# Power_Management.net
KiCad netlist of a schematic drawn in Altium Designer
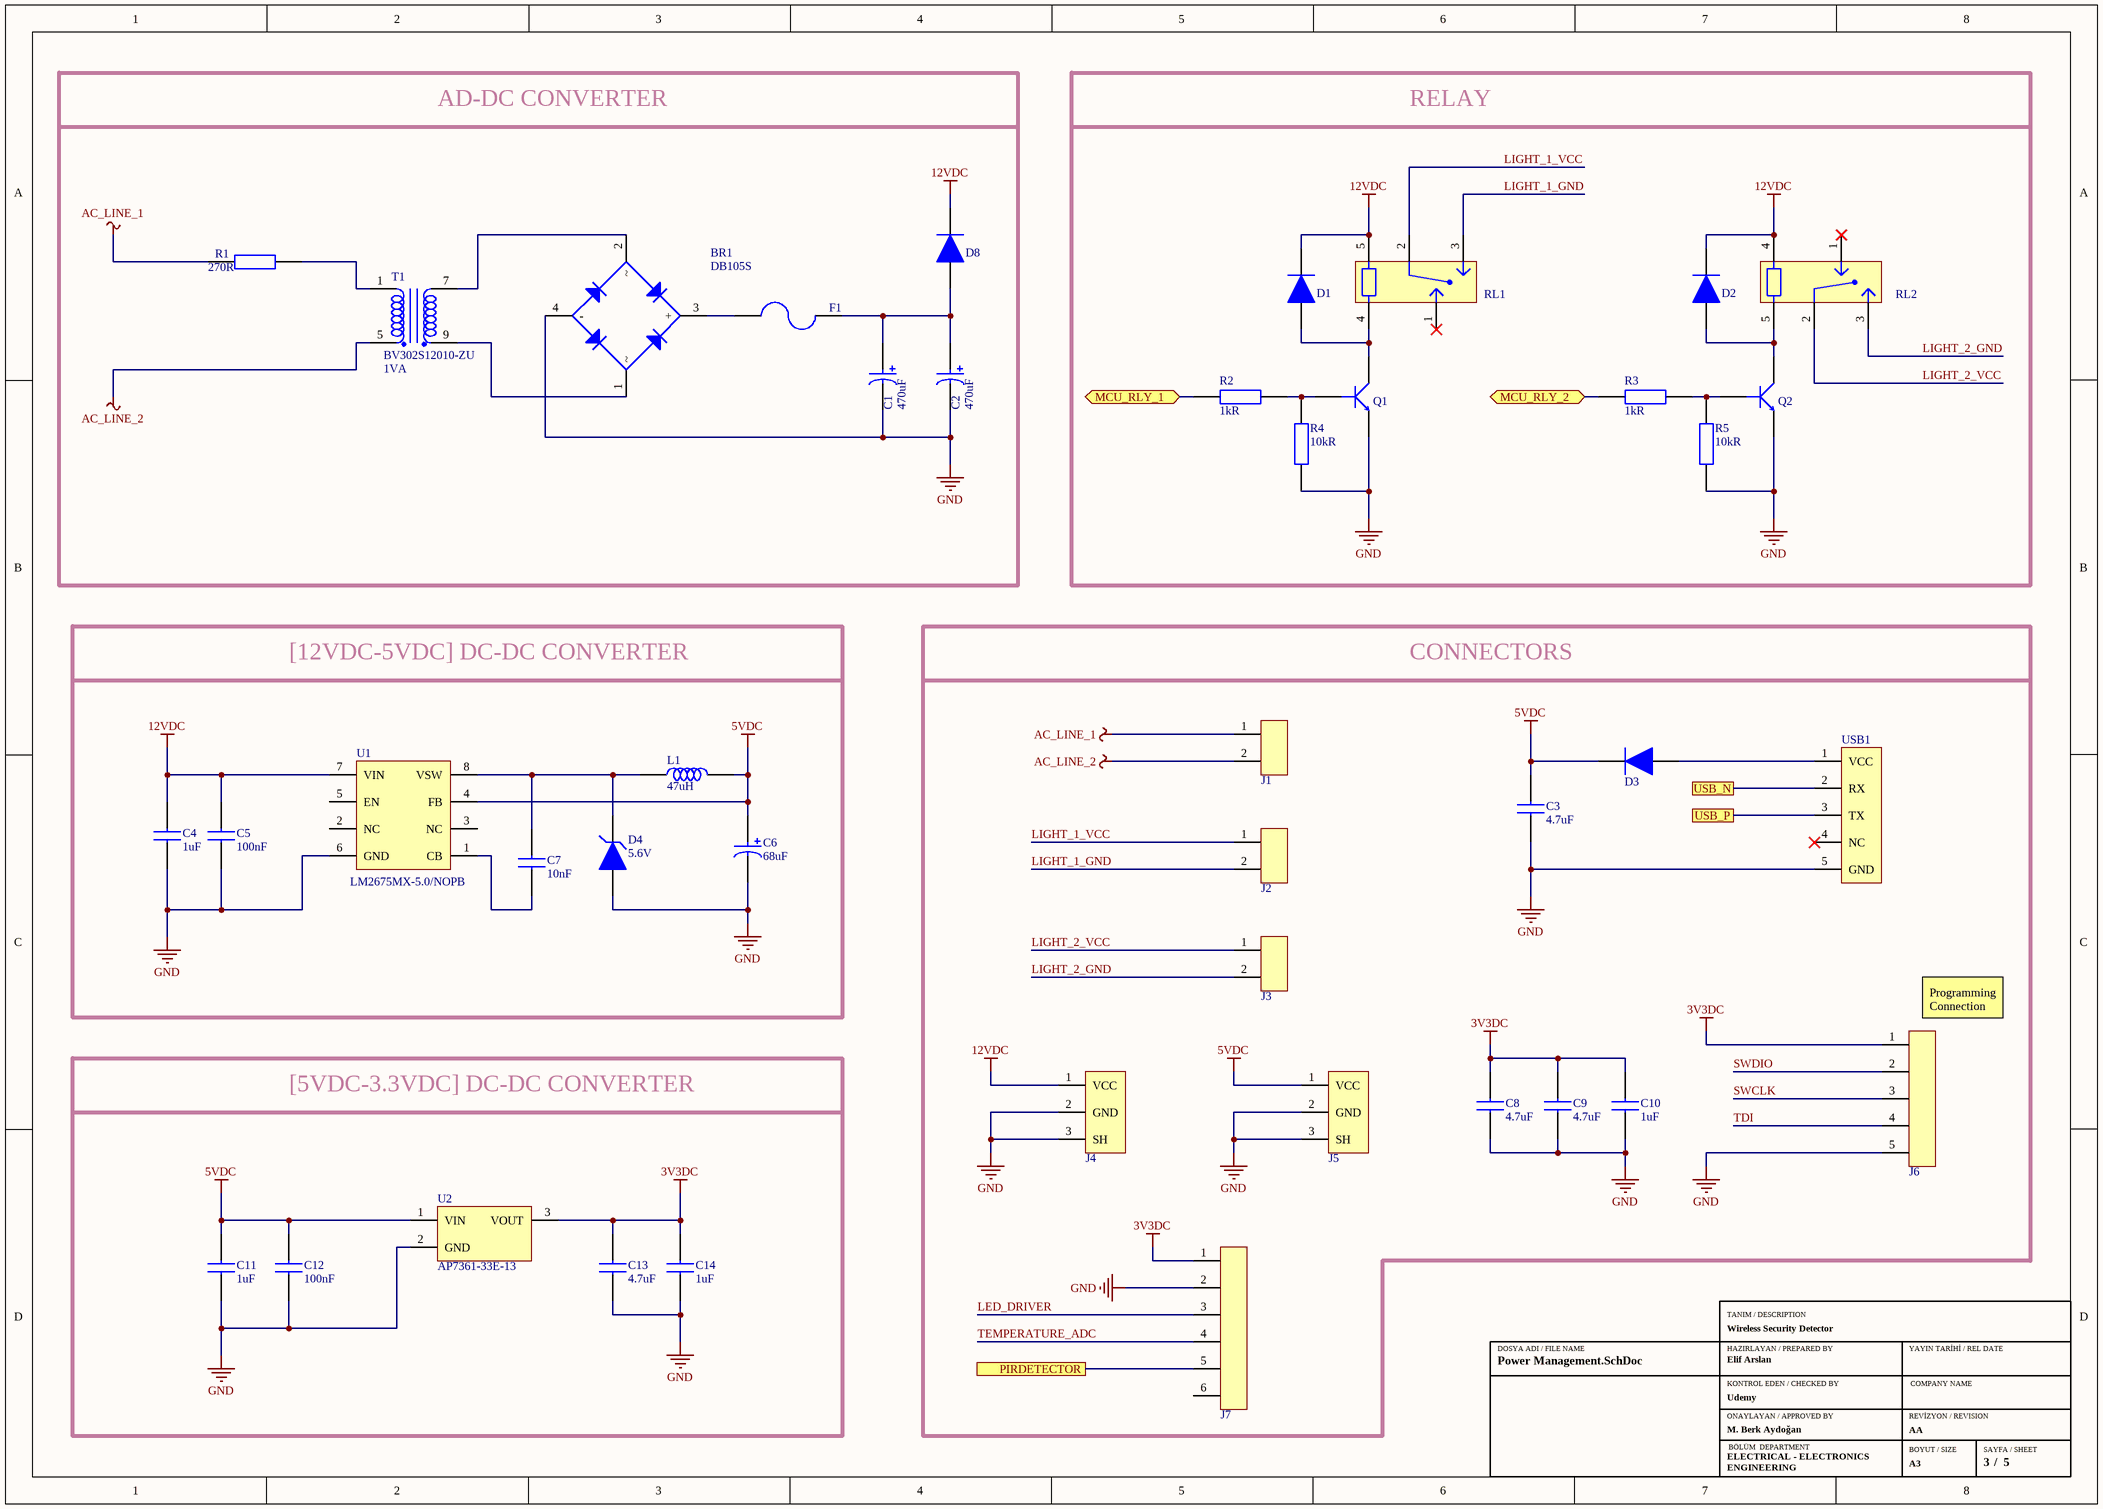
[diagram p0: Power Management.SchDoc]

(export (version "E")
  (design (tool "Eeschema 10.0.6"))
  (components
    (comp (ref "BR1")
      (value "DB105S")
      (footprint "DB105S")
      (description "Bridge Rect 1PHASE 600V 1A Db-s")
      (fields (field (name "MANUFACTURER") "Sangdest Microelectronics"))
      (libsource (lib "UDEMY_Library") (part "DB105S"))
    )
    (comp (ref "C1")
      (value "ESH477M050AL3AA")
      (footprint "CAP_RADIAL_D10_P5")
      (description "CAP ALUM 470UF 20% 50V RADIAL")
      (fields
        (field (name "MANUFACTURER") "KEMET")
        (field (name "TOLERANCE") "20%")
        (field (name "CAPACITANCE") "470uF")
      )
      (libsource (lib "UDEMY_Library") (part "CAP ALU ELEC 470uF 50V"))
    )
    (comp (ref "C2")
      (value "ESH477M050AL3AA")
      (footprint "CAP_RADIAL_D10_P5")
      (description "CAP ALUM 470UF 20% 50V RADIAL")
      (fields
        (field (name "MANUFACTURER") "KEMET")
        (field (name "TOLERANCE") "20%")
        (field (name "CAPACITANCE") "470uF")
      )
      (libsource (lib "UDEMY_Library") (part "CAP ALU ELEC 470uF 50V"))
    )
    (comp (ref "C3")
      (value "CL21A475KAQNNNE")
      (footprint "CAP_0805")
      (description "CAP CER 4.7UF 25V X5R %10 0805")
      (fields
        (field (name "MANUFACTURER") "Samsung")
        (field (name "TOLERANCE") "10%")
        (field (name "CAPACITANCE") "4.7uF")
      )
      (libsource (lib "UDEMY_Library") (part "CAP CER  4.7uF 0805"))
    )
    (comp (ref "C4")
      (value "CL21B105KBFNNNE")
      (footprint "CAP_0805")
      (description "CAP CER 1UF %10 50V 0805")
      (fields
        (field (name "MANUFACTURER") "Samsung")
        (field (name "TOLERANCE") "10%")
        (field (name "CAPACITANCE") "1uF")
      )
      (libsource (lib "UDEMY_Library") (part "CAP CER 1uF 0805"))
    )
    (comp (ref "C5")
      (value "CL21B104KBCNNNC")
      (footprint "CAP_0805")
      (description "CAP CER 0.1UF  %10 50V X7R  0805")
      (fields
        (field (name "MANUFACTURER") "Samsung")
        (field (name "TOLERANCE") "10%")
        (field (name "CAPACITANCE") "100nF")
      )
      (libsource (lib "UDEMY_Library") (part "CAP CER 100nF 0805"))
    )
    (comp (ref "C6")
      (value "EEV686M035A9HAA")
      (footprint "CAP_EEVseries")
      (description "CAP ALUM 68UF 20% 35V SMD")
      (fields
        (field (name "MANUFACTURER") "KEMET")
        (field (name "TOLERANCE") "20%")
        (field (name "CAPACITANCE") "68uF")
      )
      (libsource (lib "UDEMY_Library") (part "CAP ALU 68uF"))
    )
    (comp (ref "C7")
      (value "0603B103K160CT")
      (footprint "CAP_0603")
      (description "CAP CER 10nF %10 0603")
      (fields
        (field (name "MANUFACTURER") "Walsin Technologies")
        (field (name "TOLERANCE") "10%")
        (field (name "CAPACITANCE") "10nF")
      )
      (libsource (lib "UDEMY_Library") (part "CAP CER 10nF 0603"))
    )
    (comp (ref "C8")
      (value "CL21A475KAQNNNE")
      (footprint "CAP_0805")
      (description "CAP CER 4.7UF 25V X5R %10 0805")
      (fields
        (field (name "MANUFACTURER") "Samsung")
        (field (name "TOLERANCE") "10%")
        (field (name "CAPACITANCE") "4.7uF")
      )
      (libsource (lib "UDEMY_Library") (part "CAP CER  4.7uF 0805"))
    )
    (comp (ref "C9")
      (value "CL21A475KAQNNNE")
      (footprint "CAP_0805")
      (description "CAP CER 4.7UF 25V X5R %10 0805")
      (fields
        (field (name "MANUFACTURER") "Samsung")
        (field (name "TOLERANCE") "10%")
        (field (name "CAPACITANCE") "4.7uF")
      )
      (libsource (lib "UDEMY_Library") (part "CAP CER  4.7uF 0805"))
    )
    (comp (ref "C10")
      (value "CL21B105KBFNNNE")
      (footprint "CAP_0805")
      (description "CAP CER 1UF %10 50V 0805")
      (fields
        (field (name "MANUFACTURER") "Samsung")
        (field (name "TOLERANCE") "10%")
        (field (name "CAPACITANCE") "1uF")
      )
      (libsource (lib "UDEMY_Library") (part "CAP CER 1uF 0805"))
    )
    (comp (ref "C11")
      (value "CL21B105KBFNNNE")
      (footprint "CAP_0805")
      (description "CAP CER 1UF %10 50V 0805")
      (fields
        (field (name "MANUFACTURER") "Samsung")
        (field (name "TOLERANCE") "10%")
        (field (name "CAPACITANCE") "1uF")
      )
      (libsource (lib "UDEMY_Library") (part "CAP CER 1uF 0805"))
    )
    (comp (ref "C12")
      (value "C0603C104K4RACTU")
      (footprint "CAP_0603")
      (description "CAP CER 100nF %10 0603 SMD")
      (fields
        (field (name "MANUFACTURER") "KEMET")
        (field (name "TOLERANCE") "10%")
        (field (name "CAPACITANCE") "100nF")
      )
      (libsource (lib "UDEMY_Library") (part "CAP CER 100nF 0603"))
    )
    (comp (ref "C13")
      (value "CL21A475KAQNNNE")
      (footprint "CAP_0805")
      (description "CAP CER 4.7UF 25V X5R %10 0805")
      (fields
        (field (name "MANUFACTURER") "Samsung")
        (field (name "TOLERANCE") "10%")
        (field (name "CAPACITANCE") "4.7uF")
      )
      (libsource (lib "UDEMY_Library") (part "CAP CER  4.7uF 0805"))
    )
    (comp (ref "C14")
      (value "CL21B105KBFNNNE")
      (footprint "CAP_0805")
      (description "CAP CER 1UF %10 50V 0805")
      (fields
        (field (name "MANUFACTURER") "Samsung")
        (field (name "TOLERANCE") "10%")
        (field (name "CAPACITANCE") "1uF")
      )
      (libsource (lib "UDEMY_Library") (part "CAP CER 1uF 0805"))
    )
    (comp (ref "D1")
      (value "1N4148WS")
      (footprint "SOD323F")
      (description "VR=75V IF=150mA Trr=4ns P=200mW")
      (fields (field (name "MANUFACTURER") "ON Semiconductor / Fairchild"))
      (libsource (lib "UDEMY_Library") (part "1N4148WS"))
    )
    (comp (ref "D2")
      (value "1N4148WS")
      (footprint "SOD323F")
      (description "VR=75V IF=150mA Trr=4ns P=200mW")
      (fields (field (name "MANUFACTURER") "ON Semiconductor / Fairchild"))
      (libsource (lib "UDEMY_Library") (part "1N4148WS"))
    )
    (comp (ref "D3")
      (value "1N4148WS")
      (footprint "SOD323F")
      (description "VR=75V IF=150mA Trr=4ns P=200mW")
      (fields (field (name "MANUFACTURER") "ON Semiconductor / Fairchild"))
      (libsource (lib "UDEMY_Library") (part "1N4148WS"))
    )
    (comp (ref "D4")
      (value "1SMB5919BT3G")
      (footprint "SMB")
      (description "Zener Diode 5.6 V 3 W ±5% Surface Mount SMB")
      (fields
        (field (name "MANUFACTURER") "ON Semiconductor")
        (field (name "TOLERANCE") "5%")
        (field (name "VOLTAGE RATING (DC)") "5.6V")
      )
      (libsource (lib "UDEMY_Library") (part "1SMB5919BT3G"))
    )
    (comp (ref "D8")
      (value "1N4148WS")
      (footprint "SOD323F")
      (description "VR=75V IF=150mA Trr=4ns P=200mW")
      (fields (field (name "MANUFACTURER") "ON Semiconductor / Fairchild"))
      (libsource (lib "UDEMY_Library") (part "1N4148WS"))
    )
    (comp (ref "F1")
      (value "FUSE 3413.0216.22")
      (footprint "3413.0216.22")
      (description "1 A 32 V AC 63 V DC Fuse Board Mount (Cartridge Style Excluded) Surface Mount 1206 (3216 Metric)")
      (fields
        (field (name "MANUFACTURER") "Schurter")
        (field (name "MANUFACTURER PART NUMBER") "3413.0216.22")
      )
      (libsource (lib "UDEMY_Library") (part "FUSE 3413.0216.22"))
    )
    (comp (ref "J1")
      (value "TBP01R1-508-02BE")
      (footprint "TBP01R1-508")
      (description "2~24 Poles, Pluggable, Receptacle, Horizontal, 5.08 Pitch, Terminal Block Connector")
      (fields (field (name "MANUFACTURER") "CUI Devices"))
      (libsource (lib "UDEMY_Library") (part "TBP01R1-508-02BE"))
    )
    (comp (ref "J2")
      (value "TBP01R1-508-02BE")
      (footprint "TBP01R1-508")
      (description "2~24 Poles, Pluggable, Receptacle, Horizontal, 5.08 Pitch, Terminal Block Connector")
      (fields (field (name "MANUFACTURER") "CUI Devices"))
      (libsource (lib "UDEMY_Library") (part "TBP01R1-508-02BE"))
    )
    (comp (ref "J3")
      (value "TBP01R1-508-02BE")
      (footprint "TBP01R1-508")
      (description "2~24 Poles, Pluggable, Receptacle, Horizontal, 5.08 Pitch, Terminal Block Connector")
      (fields (field (name "MANUFACTURER") "CUI Devices"))
      (libsource (lib "UDEMY_Library") (part "TBP01R1-508-02BE"))
    )
    (comp (ref "J4")
      (value "PJ-037AH-SMT-TR")
      (footprint "JACK")
      (description "2.0 x 6.3 mm, 5.0 A, Horizontal, Surface Mount (SMT), Dc Power Jack Connector")
      (fields (field (name "MANUFACTURER") "CUI Devices"))
      (libsource (lib "UDEMY_Library") (part "PJ-037AH-SMT-TR"))
    )
    (comp (ref "J5")
      (value "PJ-037AH-SMT-TR")
      (footprint "JACK")
      (description "2.0 x 6.3 mm, 5.0 A, Horizontal, Surface Mount (SMT), Dc Power Jack Connector")
      (fields (field (name "MANUFACTURER") "CUI Devices"))
      (libsource (lib "UDEMY_Library") (part "PJ-037AH-SMT-TR"))
    )
    (comp (ref "J6")
      (value "SMH-105-02-L-S")
      (footprint "PINHEADER_1x5_RA")
      (description "5 Position Receptacle Connector 0.100\" (2.54mm) Surface Mount, Right Angle Gold")
      (fields (field (name "MANUFACTURER") "Samtec"))
      (libsource (lib "UDEMY_Library") (part "SMH-105-02-L-S"))
    )
    (comp (ref "J7")
      (value "64800611622")
      (footprint "64800611622")
      (description "1.5mm 6PIN Connector")
      (fields (field (name "MANUFACTURER") "Wurth Electronics"))
      (libsource (lib "UDEMY_Library") (part "64800611622_conn_6pin"))
    )
    (comp (ref "L1")
      (value "78438335470")
      (footprint "IND_1212")
      (description "47 µH Shielded Molded Inductor 390 mA 2.3Ohm Max 1212 (3030 Metric)")
      (fields
        (field (name "MANUFACTURER") "Wurth Electronics")
        (field (name "TOLERANCE") "30%")
        (field (name "INDUCTANCE") "47uH")
      )
      (libsource (lib "UDEMY_Library") (part "IND 47uH"))
    )
    (comp (ref "Q1")
      (value "MMBT3904-7-F")
      (footprint "SOT-23F")
      (description "Bipolar (BJT) Transistor NPN 40 V 200 mA 300MHz 300 mW Surface Mount SOT-23-3")
      (fields (field (name "MANUFACTURER") "Diodes Zetex"))
      (libsource (lib "UDEMY_Library") (part "MMBT3904-7-F"))
    )
    (comp (ref "Q2")
      (value "MMBT3904-7-F")
      (footprint "SOT-23F")
      (description "Bipolar (BJT) Transistor NPN 40 V 200 mA 300MHz 300 mW Surface Mount SOT-23-3")
      (fields (field (name "MANUFACTURER") "Diodes Zetex"))
      (libsource (lib "UDEMY_Library") (part "MMBT3904-7-F"))
    )
    (comp (ref "R1")
      (value "5WD27")
      (footprint "RES_AXIAL_W")
      (description "270 mOhms ±5% 5W Through Hole Resistor Axial - Wirewound")
      (fields
        (field (name "MANUFACTURER") "NTE Electronics")
        (field (name "TOLERANCE") "5%")
        (field (name "RESISTANCE") "270R")
      )
      (libsource (lib "UDEMY_Library") (part "5WD27"))
    )
    (comp (ref "R2")
      (value "RC0603FR-071KL")
      (footprint "RES_0603")
      (description "RES SMD 1K OHM %1 0603")
      (fields
        (field (name "MANUFACTURER") "Yageo")
        (field (name "TOLERANCE") "1%")
        (field (name "RESISTANCE") "1kR")
      )
      (libsource (lib "UDEMY_Library") (part "RES 1K OHM 0603"))
    )
    (comp (ref "R3")
      (value "RC0603FR-071KL")
      (footprint "RES_0603")
      (description "RES SMD 1K OHM %1 0603")
      (fields
        (field (name "MANUFACTURER") "Yageo")
        (field (name "TOLERANCE") "1%")
        (field (name "RESISTANCE") "1kR")
      )
      (libsource (lib "UDEMY_Library") (part "RES 1K OHM 0603"))
    )
    (comp (ref "R4")
      (value "RC0603FR-0710KL")
      (footprint "RES_0603")
      (description "RES 10K %1 OHM 0603 SMD")
      (fields
        (field (name "MANUFACTURER") "Yageo")
        (field (name "TOLERANCE") "1%")
        (field (name "RESISTANCE") "10kR")
      )
      (libsource (lib "UDEMY_Library") (part "RES 10K OHM 0603"))
    )
    (comp (ref "R5")
      (value "RC0603FR-0710KL")
      (footprint "RES_0603")
      (description "RES 10K %1 OHM 0603 SMD")
      (fields
        (field (name "MANUFACTURER") "Yageo")
        (field (name "TOLERANCE") "1%")
        (field (name "RESISTANCE") "10kR")
      )
      (libsource (lib "UDEMY_Library") (part "RES 10K OHM 0603"))
    )
    (comp (ref "RL1")
      (value "ALQ112")
      (footprint "ALQ112")
      (description "RELAY GEN PURPOSE SPDT 10A 12V")
      (fields (field (name "MANUFACTURER") "Panasonic"))
      (libsource (lib "") (part "ALQ112_1"))
    )
    (comp (ref "RL2")
      (value "ALQ112")
      (footprint "ALQ112")
      (description "RELAY GEN PURPOSE SPDT 10A 12V")
      (fields (field (name "MANUFACTURER") "Panasonic"))
      (libsource (lib "UDEMY_Library") (part "ALQ112"))
    )
    (comp (ref "T1")
      (value "BV302S12010-ZU")
      (footprint "BV302S")
      (description "230-12 Transformer 1VA")
      (fields (field (name "MANUFACTURER") "Zettler Magnetics") (field (name "RATED POWER") "1VA"))
      (libsource (lib "UDEMY_Library") (part "BV302S12010-ZU"))
    )
    (comp (ref "U1")
      (value "LM2675MX-5.0/NOPB")
      (footprint "SOIC8")
      (description "IC REG BUCK 5V 1A 8SOIC")
      (fields (field (name "MANUFACTURER") "TI National Semiconductor"))
      (libsource (lib "UDEMY_Library") (part "LM2675MX-5.0/NOPB"))
    )
    (comp (ref "U2")
      (value "AP7361-33E-13")
      (footprint "SOT-223")
      (description "AP7361 Series 3.3 V 1 A Low SMT Dropout Fixed-Mode Regulator - SOT-223")
      (fields (field (name "MANUFACTURER") "Diodes"))
      (libsource (lib "UDEMY_Library") (part "AP7361-33E-13"))
    )
    (comp (ref "USB1")
      (value "10118192-0001LF")
      (footprint "MICRO_B_USB")
      (description "CONN RCPT USB2.0 MICRO B SMD R/A")
      (fields (field (name "MANUFACTURER") "AMPHENOL ICC (FCI)"))
      (libsource (lib "UDEMY_Library") (part "Micro B USB Connector"))
    )
  )
  (nets
    (net (code "1") (name "/LED_DRIVER") (class "Default")
      (node (ref "J7") (pin "3") (pinfunction "3_3") (pintype "passive"))
    )
    (net (code "2") (name "/LIGHT_1_GND") (class "Default")
      (node (ref "J2") (pin "2") (pinfunction "2_2") (pintype "power_in"))
      (node (ref "RL1") (pin "3") (pinfunction "3_3") (pintype "passive"))
    )
    (net (code "3") (name "/LIGHT_1_VCC") (class "Default")
      (node (ref "J2") (pin "1") (pinfunction "1_1") (pintype "power_in"))
      (node (ref "RL1") (pin "2") (pinfunction "2_2") (pintype "passive"))
    )
    (net (code "4") (name "/LIGHT_2_GND") (class "Default")
      (node (ref "J3") (pin "2") (pinfunction "2_2") (pintype "power_in"))
      (node (ref "RL2") (pin "3") (pinfunction "3_3") (pintype "passive"))
    )
    (net (code "5") (name "/LIGHT_2_VCC") (class "Default")
      (node (ref "J3") (pin "1") (pinfunction "1_1") (pintype "power_in"))
      (node (ref "RL2") (pin "2") (pinfunction "2_2") (pintype "passive"))
    )
    (net (code "6") (name "/MCU_RLY_1") (class "Default")
      (node (ref "R2") (pin "1") (pinfunction "1_1") (pintype "passive"))
    )
    (net (code "7") (name "/MCU_RLY_2") (class "Default")
      (node (ref "R3") (pin "1") (pinfunction "1_1") (pintype "passive"))
    )
    (net (code "8") (name "/PIRDETECTOR") (class "Default")
      (node (ref "J7") (pin "5") (pinfunction "5_5") (pintype "passive"))
    )
    (net (code "9") (name "/SWCLK") (class "Default")
      (node (ref "J6") (pin "3") (pinfunction "3_3") (pintype "passive"))
    )
    (net (code "10") (name "/SWDIO") (class "Default")
      (node (ref "J6") (pin "2") (pinfunction "2_2") (pintype "passive"))
    )
    (net (code "11") (name "/TDI") (class "Default")
      (node (ref "J6") (pin "4") (pinfunction "4_4") (pintype "passive"))
    )
    (net (code "12") (name "/TEMPERATURE_ADC") (class "Default")
      (node (ref "J7") (pin "4") (pinfunction "4_4") (pintype "passive"))
    )
    (net (code "13") (name "/USB_N") (class "Default")
      (node (ref "USB1") (pin "2") (pinfunction "RX_2") (pintype "passive"))
    )
    (net (code "14") (name "/USB_P") (class "Default")
      (node (ref "USB1") (pin "3") (pinfunction "TX_3") (pintype "passive"))
    )
    (net (code "15") (name "3V3DC") (class "Default")
      (node (ref "C10") (pin "2") (pinfunction "2_2") (pintype "passive"))
      (node (ref "C13") (pin "2") (pinfunction "2_2") (pintype "passive"))
      (node (ref "C14") (pin "2") (pinfunction "2_2") (pintype "passive"))
      (node (ref "C8") (pin "2") (pinfunction "2_2") (pintype "passive"))
      (node (ref "C9") (pin "2") (pinfunction "2_2") (pintype "passive"))
      (node (ref "J6") (pin "1") (pinfunction "1_1") (pintype "passive"))
      (node (ref "J7") (pin "1") (pinfunction "1_1") (pintype "passive"))
      (node (ref "U2") (pin "3") (pinfunction "VOUT_3") (pintype "passive"))
    )
    (net (code "16") (name "5VDC") (class "Default")
      (node (ref "C11") (pin "2") (pinfunction "2_2") (pintype "passive"))
      (node (ref "C12") (pin "2") (pinfunction "2_2") (pintype "passive"))
      (node (ref "C3") (pin "2") (pinfunction "2_2") (pintype "passive"))
      (node (ref "C6") (pin "1") (pinfunction "1_1") (pintype "passive"))
      (node (ref "D3") (pin "1") (pinfunction "1_1") (pintype "passive"))
      (node (ref "J5") (pin "1") (pinfunction "VCC_1") (pintype "power_in"))
      (node (ref "L1") (pin "2") (pinfunction "2_2") (pintype "passive"))
      (node (ref "U1") (pin "4") (pinfunction "FB_4") (pintype "passive"))
      (node (ref "U2") (pin "1") (pinfunction "VIN_1") (pintype "passive"))
    )
    (net (code "17") (name "12VDC") (class "Default")
      (node (ref "C4") (pin "2") (pinfunction "2_2") (pintype "passive"))
      (node (ref "C5") (pin "2") (pinfunction "2_2") (pintype "passive"))
      (node (ref "D1") (pin "1") (pinfunction "1_1") (pintype "passive"))
      (node (ref "D2") (pin "1") (pinfunction "1_1") (pintype "passive"))
      (node (ref "D8") (pin "1") (pinfunction "1_1") (pintype "passive"))
      (node (ref "J4") (pin "1") (pinfunction "VCC_1") (pintype "power_in"))
      (node (ref "RL1") (pin "5") (pinfunction "5_5") (pintype "passive"))
      (node (ref "RL2") (pin "4") (pinfunction "4_4") (pintype "passive"))
      (node (ref "U1") (pin "7") (pinfunction "VIN_7") (pintype "passive"))
    )
    (net (code "18") (name "AC_LINE_1") (class "Default")
      (node (ref "J1") (pin "1") (pinfunction "1_1") (pintype "power_in"))
      (node (ref "R1") (pin "1") (pinfunction "1_1") (pintype "passive"))
    )
    (net (code "19") (name "AC_LINE_2") (class "Default")
      (node (ref "J1") (pin "2") (pinfunction "2_2") (pintype "power_in"))
      (node (ref "T1") (pin "5") (pinfunction "5_5") (pintype "passive"))
    )
    (net (code "20") (name "GND") (class "Default")
      (node (ref "BR1") (pin "4") (pinfunction "-_4") (pintype "passive"))
      (node (ref "C1") (pin "2") (pinfunction "2_2") (pintype "passive"))
      (node (ref "C10") (pin "1") (pinfunction "1_1") (pintype "passive"))
      (node (ref "C11") (pin "1") (pinfunction "1_1") (pintype "passive"))
      (node (ref "C12") (pin "1") (pinfunction "1_1") (pintype "passive"))
      (node (ref "C13") (pin "1") (pinfunction "1_1") (pintype "passive"))
      (node (ref "C14") (pin "1") (pinfunction "1_1") (pintype "passive"))
      (node (ref "C2") (pin "2") (pinfunction "2_2") (pintype "passive"))
      (node (ref "C3") (pin "1") (pinfunction "1_1") (pintype "passive"))
      (node (ref "C4") (pin "1") (pinfunction "1_1") (pintype "passive"))
      (node (ref "C5") (pin "1") (pinfunction "1_1") (pintype "passive"))
      (node (ref "C6") (pin "2") (pinfunction "2_2") (pintype "passive"))
      (node (ref "C8") (pin "1") (pinfunction "1_1") (pintype "passive"))
      (node (ref "C9") (pin "1") (pinfunction "1_1") (pintype "passive"))
      (node (ref "D4") (pin "A") (pinfunction "A_A") (pintype "passive"))
      (node (ref "J4") (pin "2") (pinfunction "GND_2") (pintype "power_in"))
      (node (ref "J4") (pin "3") (pinfunction "SH_3") (pintype "power_in"))
      (node (ref "J5") (pin "2") (pinfunction "GND_2") (pintype "power_in"))
      (node (ref "J5") (pin "3") (pinfunction "SH_3") (pintype "power_in"))
      (node (ref "J6") (pin "5") (pinfunction "5_5") (pintype "passive"))
      (node (ref "J7") (pin "2") (pinfunction "2_2") (pintype "passive"))
      (node (ref "Q1") (pin "2") (pinfunction "E_2") (pintype "passive"))
      (node (ref "Q2") (pin "2") (pinfunction "E_2") (pintype "passive"))
      (node (ref "R4") (pin "1") (pinfunction "1_1") (pintype "passive"))
      (node (ref "R5") (pin "1") (pinfunction "1_1") (pintype "passive"))
      (node (ref "U1") (pin "6") (pinfunction "GND_6") (pintype "passive"))
      (node (ref "U2") (pin "2") (pinfunction "GND_2") (pintype "passive"))
      (node (ref "USB1") (pin "5") (pinfunction "GND_5") (pintype "passive"))
    )
    (net (code "21") (name "Net-(BR1-+)") (class "Default")
      (node (ref "BR1") (pin "3") (pinfunction "+_3") (pintype "passive"))
      (node (ref "F1") (pin "1") (pinfunction "1_1") (pintype "passive"))
    )
    (net (code "22") (name "Net-(BR1-~-Pad1)") (class "Default")
      (node (ref "BR1") (pin "1") (pinfunction "~_1") (pintype "passive"))
      (node (ref "T1") (pin "9") (pinfunction "9_9") (pintype "passive"))
    )
    (net (code "23") (name "Net-(BR1-~-Pad2)") (class "Default")
      (node (ref "BR1") (pin "2") (pinfunction "~_2") (pintype "passive"))
      (node (ref "T1") (pin "7") (pinfunction "7_7") (pintype "passive"))
    )
    (net (code "24") (name "Net-(C1-Pad1)") (class "Default")
      (node (ref "C1") (pin "1") (pinfunction "1_1") (pintype "passive"))
      (node (ref "C2") (pin "1") (pinfunction "1_1") (pintype "passive"))
      (node (ref "D8") (pin "2") (pinfunction "2_2") (pintype "passive"))
      (node (ref "F1") (pin "2") (pinfunction "2_2") (pintype "passive"))
    )
    (net (code "25") (name "Net-(Q1-B)") (class "Default")
      (node (ref "Q1") (pin "1") (pinfunction "B_1") (pintype "passive"))
      (node (ref "R2") (pin "2") (pinfunction "2_2") (pintype "passive"))
      (node (ref "R4") (pin "2") (pinfunction "2_2") (pintype "passive"))
    )
    (net (code "26") (name "Net-(Q1-C)") (class "Default")
      (node (ref "D1") (pin "2") (pinfunction "2_2") (pintype "passive"))
      (node (ref "Q1") (pin "3") (pinfunction "C_3") (pintype "passive"))
      (node (ref "RL1") (pin "4") (pinfunction "4_4") (pintype "passive"))
    )
    (net (code "27") (name "Net-(Q2-B)") (class "Default")
      (node (ref "Q2") (pin "1") (pinfunction "B_1") (pintype "passive"))
      (node (ref "R3") (pin "2") (pinfunction "2_2") (pintype "passive"))
      (node (ref "R5") (pin "2") (pinfunction "2_2") (pintype "passive"))
    )
    (net (code "28") (name "Net-(Q2-C)") (class "Default")
      (node (ref "D2") (pin "2") (pinfunction "2_2") (pintype "passive"))
      (node (ref "Q2") (pin "3") (pinfunction "C_3") (pintype "passive"))
      (node (ref "RL2") (pin "5") (pinfunction "5_5") (pintype "passive"))
    )
    (net (code "29") (name "Net-(R1-Pad2)") (class "Default")
      (node (ref "R1") (pin "2") (pinfunction "2_2") (pintype "passive"))
      (node (ref "T1") (pin "1") (pinfunction "1_1") (pintype "passive"))
    )
    (net (code "30") (name "Net-(U1-CB)") (class "Default")
      (node (ref "C7") (pin "1") (pinfunction "1_1") (pintype "passive"))
      (node (ref "U1") (pin "1") (pinfunction "CB_1") (pintype "passive"))
    )
    (net (code "31") (name "Net-(U1-VSW)") (class "Default")
      (node (ref "C7") (pin "2") (pinfunction "2_2") (pintype "passive"))
      (node (ref "D4") (pin "C") (pinfunction "C_C") (pintype "passive"))
      (node (ref "L1") (pin "1") (pinfunction "1_1") (pintype "passive"))
      (node (ref "U1") (pin "8") (pinfunction "VSW_8") (pintype "passive"))
    )
    (net (code "32") (name "Net-(USB1-VCC)") (class "Default")
      (node (ref "D3") (pin "2") (pinfunction "2_2") (pintype "passive"))
      (node (ref "USB1") (pin "1") (pinfunction "VCC_1") (pintype "passive"))
    )
    (net (code "33") (name "unconnected-(J7-Pad6)") (class "Default")
      (node (ref "J7") (pin "6") (pinfunction "6_6") (pintype "passive"))
    )
    (net (code "34") (name "unconnected-(RL1-Pad1)") (class "Default")
      (node (ref "RL1") (pin "1") (pinfunction "1_1") (pintype "passive+no_connect"))
    )
    (net (code "35") (name "unconnected-(RL2-Pad1)") (class "Default")
      (node (ref "RL2") (pin "1") (pinfunction "1_1") (pintype "passive+no_connect"))
    )
    (net (code "36") (name "unconnected-(U1-EN-Pad5)") (class "Default")
      (node (ref "U1") (pin "5") (pinfunction "EN_5") (pintype "passive"))
    )
    (net (code "37") (name "unconnected-(U1-NC-Pad2)") (class "Default")
      (node (ref "U1") (pin "2") (pinfunction "NC_2") (pintype "passive"))
    )
    (net (code "38") (name "unconnected-(U1-NC-Pad3)") (class "Default")
      (node (ref "U1") (pin "3") (pinfunction "NC_3") (pintype "passive"))
    )
    (net (code "39") (name "unconnected-(USB1-NC-Pad4)") (class "Default")
      (node (ref "USB1") (pin "4") (pinfunction "NC_4") (pintype "passive+no_connect"))
    )
  )
)
